# Nixie_PSU.net
KiCad netlist of a schematic drawn in Altium Designer
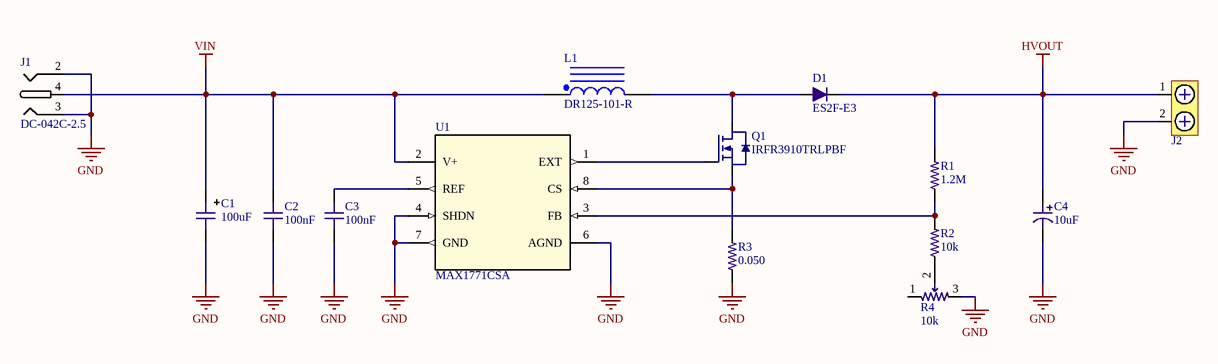
[diagram p0: Nixie_PSU.SchDoc]

(export (version "E")
  (design (tool "Eeschema 10.0.6"))
  (components
    (comp (ref "C1")
      (value "100uF")
      (footprint "C2917")
      (description "CAP TANT 100UF 25V 10% 2917")
      (fields (field (name "Comment") "TPSD107M020R0150"))
      (libsource (lib "Capacitors") (part "C2917 100uF 25V TANT"))
    )
    (comp (ref "C2")
      (value "100nF")
      (footprint "C0603-IPC")
      (description "CAP CER 0.1UF 50V X7R 0603")
      (fields (field (name "Comment") "C0603 100nF 50V X7R"))
      (libsource (lib "Capacitors") (part "C0603 100nF 50V X7R"))
    )
    (comp (ref "C3")
      (value "100nF")
      (footprint "C0603-IPC")
      (description "CAP CER 0.1UF 50V X7R 0603")
      (fields (field (name "Comment") "C0603 100nF 50V X7R"))
      (libsource (lib "Capacitors") (part "C0603 100nF 50V X7R"))
    )
    (comp (ref "C4")
      (value "10uF")
      (footprint "C-SMD-Polarized-10x10.2x17mm")
      (description "10 µF 250 V Aluminum Electrolytic Capacitors Radial, Can - SMD - 4000 Hrs @ 105°C")
      (fields (field (name "VOLTAGE") "250V") (field (name "Comment") "EEV-EB2E100Q"))
      (libsource (lib "Capacitors") (part "C-SMD 10uF 250V Electrolytic"))
    )
    (comp (ref "D1")
      (value "ES2F-E3")
      (footprint "DO-214AA")
      (description "Diode Standard 300 V 2A 35ns Trr Surface Mount DO-214AA (SMB)")
      (libsource (lib "Diodes") (part "ES2F-E3"))
    )
    (comp (ref "J1")
      (value "DC-042C-2.5")
      (footprint "DC-042C-2.5 THT BARREL JACK")
      (description "DC Power Receptacle Jack 8A 2.5mm DIP AC/DC Power Plugs & Receptacles")
      (libsource (lib "Connectors") (part "DC Barrel Jack 2.5 x 5.5mm THT"))
    )
    (comp (ref "J2")
      (value "Phoenix Contact 1935161")
      (footprint "Phoenix_1935161")
      (description "Terminal Block, 2 Position, 5mm pitch, 18A, 300V, 12-26 AWG")
      (fields
        (field (name "MANUFACTURER") "Phoenix Contact")
        (field (name "MANUFACTURER PART NUMBER") "1935161")
      )
      (libsource (lib "Connectors") (part "Term Block 2pos"))
    )
    (comp (ref "L1")
      (value "DR125-101-R")
      (footprint "EATN-DR125_V")
      (fields (field (name "MANUFACTURER") "EATON"))
      (libsource (lib "Altium Content Vault") (part "IND-DOT-2"))
    )
    (comp (ref "Q1")
      (value "IRFR3910TRLPBF")
      (footprint "DPAK2 IRFR3910")
      (description "N-Channel 16A (Tc) 79W (Tc) Surface Mount D-Pak")
      (libsource (lib "Transistors") (part "IRFR3910TRLPBF"))
    )
    (comp (ref "R1")
      (value "1.2M")
      (footprint "R1206-IPC")
      (description "1.2 MOhms ±5% 0.25W, 1/4W Chip Resistor 1206 (3216 Metric) Moisture Resistant Thick Film")
      (fields (field (name "Comment") "RC1206JR-071M2L"))
      (libsource (lib "Resistors") (part "R1206 1.2M 1%"))
    )
    (comp (ref "R2")
      (value "10k")
      (footprint "R0603-IPC-10K")
      (description "RES SMD 10K OHM 1% 1/10W 0603")
      (fields (field (name "Comment") "R0603 10K 1%"))
      (libsource (lib "Resistors") (part "R0603 10K 1%"))
    )
    (comp (ref "R3")
      (value "0.050")
      (footprint "R1206-IPC-0R050")
      (description "RES 0.05 OHM 1% 1W 1206")
      (fields (field (name "Comment") "CSNL1206FT50L0"))
      (libsource (lib "Resistors") (part "R1206 0R050 1%"))
    )
    (comp (ref "R4")
      (value "10k")
      (footprint "CT-6EP")
      (description "Trimmer, 10k, 1 Turn, Thru-Hole, Cermet, 100ppm/C")
      (fields (field (name "Comment") "Trimmer 10k 1%"))
      (libsource (lib "Resistors") (part "Trimmer 100k 1%"))
    )
    (comp (ref "U1")
      (value "MAX1771CSA")
      (footprint "SOIC-8N - MAX1771")
      (libsource (lib "Integrated Circuits") (part "MAX1771CSA"))
    )
  )
  (nets
    (net (code "1") (name "GND") (class "Default")
      (node (ref "C1") (pin "2") (pintype "passive"))
      (node (ref "C2") (pin "1") (pintype "passive"))
      (node (ref "C3") (pin "1") (pintype "passive"))
      (node (ref "C4") (pin "2") (pintype "passive"))
      (node (ref "J1") (pin "2") (pinfunction "2_2") (pintype "passive"))
      (node (ref "J1") (pin "3") (pinfunction "3_3") (pintype "passive"))
      (node (ref "J2") (pin "2") (pintype "passive"))
      (node (ref "R3") (pin "1") (pintype "passive"))
      (node (ref "R4") (pin "3") (pintype "passive"))
      (node (ref "U1") (pin "4") (pinfunction "SHDN_4") (pintype "input"))
      (node (ref "U1") (pin "6") (pinfunction "AGND_6") (pintype "power_in"))
      (node (ref "U1") (pin "7") (pinfunction "GND_7") (pintype "output"))
    )
    (net (code "2") (name "HVOUT") (class "Default")
      (node (ref "C4") (pin "1") (pintype "passive"))
      (node (ref "D1") (pin "1") (pinfunction "1_1") (pintype "passive"))
      (node (ref "J2") (pin "1") (pintype "passive"))
      (node (ref "R1") (pin "2") (pintype "passive"))
    )
    (net (code "3") (name "Net-(Q1-D)") (class "Default")
      (node (ref "D1") (pin "2") (pinfunction "2_2") (pintype "passive"))
      (node (ref "L1") (pin "2") (pinfunction "2_2") (pintype "passive"))
      (node (ref "Q1") (pin "2") (pinfunction "D_2") (pintype "passive"))
    )
    (net (code "4") (name "Net-(Q1-G)") (class "Default")
      (node (ref "Q1") (pin "1") (pinfunction "G_1") (pintype "passive"))
      (node (ref "U1") (pin "1") (pinfunction "EXT_1") (pintype "output"))
    )
    (net (code "5") (name "Net-(Q1-S)") (class "Default")
      (node (ref "Q1") (pin "3") (pinfunction "S_3") (pintype "passive"))
      (node (ref "R3") (pin "2") (pintype "passive"))
      (node (ref "U1") (pin "8") (pinfunction "CS_8") (pintype "input"))
    )
    (net (code "6") (name "Net-(R4-W)") (class "Default")
      (node (ref "R2") (pin "1") (pintype "passive"))
      (node (ref "R4") (pin "2") (pinfunction "W_2") (pintype "passive"))
    )
    (net (code "7") (name "Net-(U1-FB)") (class "Default")
      (node (ref "R1") (pin "1") (pintype "passive"))
      (node (ref "R2") (pin "2") (pintype "passive"))
      (node (ref "U1") (pin "3") (pinfunction "FB_3") (pintype "input"))
    )
    (net (code "8") (name "Net-(U1-REF)") (class "Default")
      (node (ref "C3") (pin "2") (pintype "passive"))
      (node (ref "U1") (pin "5") (pinfunction "REF_5") (pintype "output"))
    )
    (net (code "9") (name "VIN") (class "Default")
      (node (ref "C1") (pin "1") (pintype "passive"))
      (node (ref "C2") (pin "2") (pintype "passive"))
      (node (ref "J1") (pin "4") (pinfunction "4_4") (pintype "passive"))
      (node (ref "L1") (pin "1") (pinfunction "1_1") (pintype "passive"))
      (node (ref "U1") (pin "2") (pinfunction "V+_2") (pintype "power_in"))
    )
    (net (code "10") (name "unconnected-(R4-Pad1)") (class "Default")
      (node (ref "R4") (pin "1") (pintype "passive"))
    )
  )
)
